# mast_additional_board.net
KiCad netlist of a schematic drawn in EAGLE
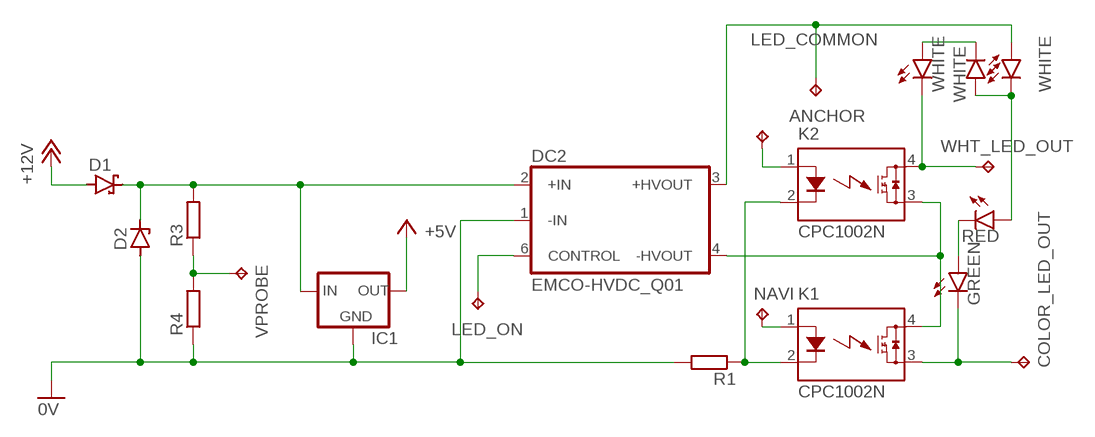
[diagram p0: schematic, sheet 1]

(export (version "E")
  (design (tool "Eeschema 10.0.6"))
  (components
    (comp (ref "ANCHOR")
      (value "TPPAD1-13")
      (footprint "eagle-import:P1-13")
      (libsource (lib "eagle-import") (part "TPPAD1-13"))
    )
    (comp (ref "COLOR_LED_OUT")
      (value "TPPAD1-13")
      (footprint "eagle-import:P1-13")
      (libsource (lib "eagle-import") (part "TPPAD1-13"))
    )
    (comp (ref "D1")
      (value "SCHOTTKY-DIODEC4111-15")
      (footprint "eagle-import:C4111-15")
      (libsource (lib "eagle-import") (part "SCHOTTKY-DIODEC4111-15"))
    )
    (comp (ref "D2")
      (value "ZENER-DIODEDO34-7")
      (footprint "eagle-import:DO34Z7")
      (libsource (lib "eagle-import") (part "ZENER-DIODEDO34-7"))
    )
    (comp (ref "DC2")
      (value "EMCO-HVDC_Q01")
      (footprint "eagle-import:EMCO-HVDC-Q_100-2000V")
      (libsource (lib "eagle-import") (part "EMCO-HVDC_Q?01"))
    )
    (comp (ref "IC1")
      (value "78LXX")
      (footprint "eagle-import:78LXX")
      (libsource (lib "eagle-import") (part "78LXX"))
    )
    (comp (ref "K1")
      (value "CPC1002N")
      (footprint "eagle-import:SOIC254P610X218-4N")
      (libsource (lib "eagle-import") (part "CPC1002N"))
    )
    (comp (ref "K2")
      (value "CPC1002N")
      (footprint "eagle-import:SOIC254P610X218-4N")
      (libsource (lib "eagle-import") (part "CPC1002N"))
    )
    (comp (ref "LED1")
      (value "WHITE")
      (footprint "eagle-import:LED5MM")
      (libsource (lib "eagle-import") (part "LED5MM"))
    )
    (comp (ref "LED2")
      (value "WHITE")
      (footprint "eagle-import:LED5MM")
      (libsource (lib "eagle-import") (part "LED5MM"))
    )
    (comp (ref "LED3")
      (value "WHITE")
      (footprint "eagle-import:LED5MM")
      (libsource (lib "eagle-import") (part "LED5MM"))
    )
    (comp (ref "LED5")
      (value "RED")
      (footprint "eagle-import:LED5MM")
      (libsource (lib "eagle-import") (part "LED5MM"))
    )
    (comp (ref "LED6")
      (value "GREEN")
      (footprint "eagle-import:LED5MM")
      (libsource (lib "eagle-import") (part "LED5MM"))
    )
    (comp (ref "LED_COMMON")
      (value "TPPAD1-13")
      (footprint "eagle-import:P1-13")
      (libsource (lib "eagle-import") (part "TPPAD1-13"))
    )
    (comp (ref "LED_ON")
      (value "TPPAD1-13")
      (footprint "eagle-import:P1-13")
      (libsource (lib "eagle-import") (part "TPPAD1-13"))
    )
    (comp (ref "NAVI")
      (value "TPPAD1-13")
      (footprint "eagle-import:P1-13")
      (libsource (lib "eagle-import") (part "TPPAD1-13"))
    )
    (comp (ref "R1")
      (value "R-EU_0309/12")
      (footprint "eagle-import:0309_12")
      (libsource (lib "eagle-import") (part "R-EU_0309/12"))
    )
    (comp (ref "R3")
      (value "R-EU_0309/12")
      (footprint "eagle-import:0309_12")
      (libsource (lib "eagle-import") (part "R-EU_0309/12"))
    )
    (comp (ref "R4")
      (value "R-EU_0309/12")
      (footprint "eagle-import:0309_12")
      (libsource (lib "eagle-import") (part "R-EU_0309/12"))
    )
    (comp (ref "VPROBE")
      (value "TPPAD1-13")
      (footprint "eagle-import:P1-13")
      (libsource (lib "eagle-import") (part "TPPAD1-13"))
    )
    (comp (ref "WHT_LED_OUT")
      (value "TPPAD1-13")
      (footprint "eagle-import:P1-13")
      (libsource (lib "eagle-import") (part "TPPAD1-13"))
    )
  )
  (nets
    (net (code "1") (name "+5V") (class "Default")
      (node (ref "IC1") (pin "OUT") (pinfunction "OUT_OUT") (pintype "passive"))
    )
    (net (code "2") (name "+12V") (class "Default")
      (node (ref "D1") (pin "A") (pinfunction "A_A") (pintype "passive"))
    )
    (net (code "3") (name "0V") (class "Default")
      (node (ref "D2") (pin "A") (pinfunction "A_A") (pintype "passive"))
      (node (ref "DC2") (pin "1") (pinfunction "-IN_1") (pintype "passive"))
      (node (ref "IC1") (pin "GND") (pinfunction "GND_GND") (pintype "input"))
      (node (ref "R1") (pin "2") (pinfunction "2_2") (pintype "passive"))
      (node (ref "R4") (pin "1") (pinfunction "1_1") (pintype "passive"))
    )
    (net (code "4") (name "Net-(DC2-+HVOUT)") (class "Default")
      (node (ref "DC2") (pin "3") (pinfunction "+HVOUT_3") (pintype "passive"))
      (node (ref "LED1") (pin "A") (pinfunction "A_A") (pintype "passive"))
      (node (ref "LED_COMMON") (pin "TP") (pinfunction "TP_TP") (pintype "input"))
    )
    (net (code "5") (name "Net-(DC2-+IN)") (class "Default")
      (node (ref "D1") (pin "C") (pinfunction "C_C") (pintype "passive"))
      (node (ref "D2") (pin "C") (pinfunction "C_C") (pintype "passive"))
      (node (ref "DC2") (pin "2") (pinfunction "+IN_2") (pintype "passive"))
      (node (ref "IC1") (pin "IN") (pinfunction "IN_IN") (pintype "input"))
      (node (ref "R3") (pin "2") (pinfunction "2_2") (pintype "passive"))
    )
    (net (code "6") (name "Net-(DC2--HVOUT)") (class "Default")
      (node (ref "DC2") (pin "4") (pinfunction "-HVOUT_4") (pintype "passive"))
      (node (ref "K1") (pin "4") (pinfunction "DS1_4") (pintype "passive"))
      (node (ref "K2") (pin "3") (pinfunction "DS2_3") (pintype "passive"))
    )
    (net (code "7") (name "Net-(DC2-CONTROL)") (class "Default")
      (node (ref "DC2") (pin "6") (pinfunction "CONTROL_6") (pintype "passive"))
      (node (ref "LED_ON") (pin "TP") (pinfunction "TP_TP") (pintype "input"))
    )
    (net (code "8") (name "Net-(K1-A)") (class "Default")
      (node (ref "K1") (pin "1") (pinfunction "A_1") (pintype "passive"))
      (node (ref "NAVI") (pin "TP") (pinfunction "TP_TP") (pintype "input"))
    )
    (net (code "9") (name "Net-(K1-DS2)") (class "Default")
      (node (ref "COLOR_LED_OUT") (pin "TP") (pinfunction "TP_TP") (pintype "input"))
      (node (ref "K1") (pin "3") (pinfunction "DS2_3") (pintype "passive"))
      (node (ref "LED6") (pin "K") (pinfunction "C_K") (pintype "passive"))
    )
    (net (code "10") (name "Net-(K1-K)") (class "Default")
      (node (ref "K1") (pin "2") (pinfunction "K_2") (pintype "passive"))
      (node (ref "K2") (pin "2") (pinfunction "K_2") (pintype "passive"))
      (node (ref "R1") (pin "1") (pinfunction "1_1") (pintype "passive"))
    )
    (net (code "11") (name "Net-(K2-A)") (class "Default")
      (node (ref "ANCHOR") (pin "TP") (pinfunction "TP_TP") (pintype "input"))
      (node (ref "K2") (pin "1") (pinfunction "A_1") (pintype "passive"))
    )
    (net (code "12") (name "Net-(K2-DS1)") (class "Default")
      (node (ref "K2") (pin "4") (pinfunction "DS1_4") (pintype "passive"))
      (node (ref "LED3") (pin "K") (pinfunction "C_K") (pintype "passive"))
      (node (ref "WHT_LED_OUT") (pin "TP") (pinfunction "TP_TP") (pintype "input"))
    )
    (net (code "13") (name "Net-(LED1-C)") (class "Default")
      (node (ref "LED1") (pin "K") (pinfunction "C_K") (pintype "passive"))
      (node (ref "LED2") (pin "A") (pinfunction "A_A") (pintype "passive"))
      (node (ref "LED5") (pin "A") (pinfunction "A_A") (pintype "passive"))
    )
    (net (code "14") (name "Net-(LED2-C)") (class "Default")
      (node (ref "LED2") (pin "K") (pinfunction "C_K") (pintype "passive"))
      (node (ref "LED3") (pin "A") (pinfunction "A_A") (pintype "passive"))
    )
    (net (code "15") (name "Net-(LED5-C)") (class "Default")
      (node (ref "LED5") (pin "K") (pinfunction "C_K") (pintype "passive"))
      (node (ref "LED6") (pin "A") (pinfunction "A_A") (pintype "passive"))
    )
    (net (code "16") (name "Net-(R3-Pad1)") (class "Default")
      (node (ref "R3") (pin "1") (pinfunction "1_1") (pintype "passive"))
      (node (ref "R4") (pin "2") (pinfunction "2_2") (pintype "passive"))
      (node (ref "VPROBE") (pin "TP") (pinfunction "TP_TP") (pintype "input"))
    )
  )
)
